# protractor.net
KiCad netlist of a schematic drawn in EAGLE
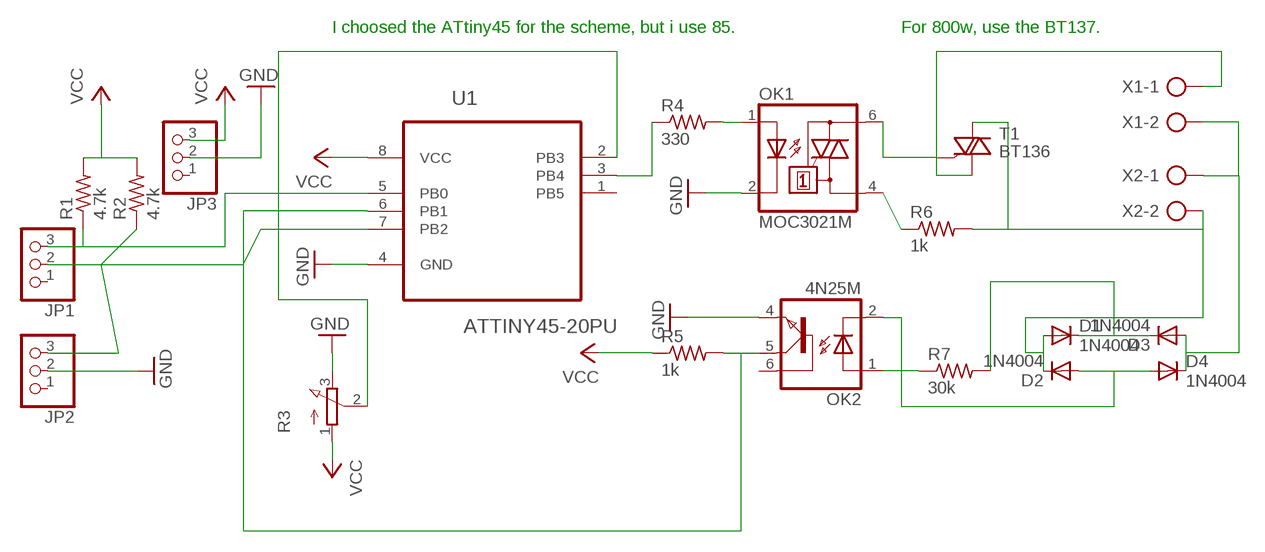
[diagram p0: schematic, sheet 1]

(export (version "E")
  (design (tool "Eeschema 10.0.6"))
  (components
    (comp (ref "D1")
      (value "1N4004")
      (footprint "eagle-import:DO41-10")
      (libsource (lib "eagle-import") (part "1N4004"))
    )
    (comp (ref "D2")
      (value "1N4004")
      (footprint "eagle-import:DO41-10")
      (libsource (lib "eagle-import") (part "1N4004"))
    )
    (comp (ref "D3")
      (value "1N4004")
      (footprint "eagle-import:DO41-10")
      (libsource (lib "eagle-import") (part "1N4004"))
    )
    (comp (ref "D4")
      (value "1N4004")
      (footprint "eagle-import:DO41-10")
      (libsource (lib "eagle-import") (part "1N4004"))
    )
    (comp (ref "JP1")
      (value "PINHD-1X3")
      (footprint "eagle-import:1X03")
      (libsource (lib "eagle-import") (part "PINHD-1X3"))
    )
    (comp (ref "JP2")
      (value "PINHD-1X3")
      (footprint "eagle-import:1X03")
      (libsource (lib "eagle-import") (part "PINHD-1X3"))
    )
    (comp (ref "JP3")
      (value "PINHD-1X3")
      (footprint "eagle-import:1X03")
      (libsource (lib "eagle-import") (part "PINHD-1X3"))
    )
    (comp (ref "OK1")
      (value "MOC3021M")
      (footprint "eagle-import:DIL06")
      (fields (field (name "MF") "FAIRCHILD SEMICONDUCTOR") (field (name "MPN") "MOC3021-M"))
      (libsource (lib "eagle-import") (part "MOC30M21"))
    )
    (comp (ref "OK2")
      (value "4N25M")
      (footprint "eagle-import:DIL06")
      (fields (field (name "MPN") "4N25-M"))
      (libsource (lib "eagle-import") (part "4N?M25"))
    )
    (comp (ref "R1")
      (value "4.7k")
      (footprint "eagle-import:0207_12")
      (libsource (lib "eagle-import") (part "R-US_0207/12"))
    )
    (comp (ref "R2")
      (value "4.7k")
      (footprint "eagle-import:0207_12")
      (libsource (lib "eagle-import") (part "R-US_0207/12"))
    )
    (comp (ref "R3")
      (value "3RP/1610N")
      (footprint "eagle-import:3RP_1610N")
      (libsource (lib "eagle-import") (part "3RP/1610N"))
    )
    (comp (ref "R4")
      (value "330")
      (footprint "eagle-import:0207_12")
      (libsource (lib "eagle-import") (part "R-US_0207/12"))
    )
    (comp (ref "R5")
      (value "1k")
      (footprint "eagle-import:0207_12")
      (libsource (lib "eagle-import") (part "R-US_0207/12"))
    )
    (comp (ref "R6")
      (value "1k")
      (footprint "eagle-import:0207_12")
      (libsource (lib "eagle-import") (part "R-US_0207/12"))
    )
    (comp (ref "R7")
      (value "30k")
      (footprint "eagle-import:0207_12")
      (libsource (lib "eagle-import") (part "R-US_0207/12"))
    )
    (comp (ref "T1")
      (value "BT136")
      (footprint "eagle-import:TO220AB")
      (libsource (lib "eagle-import") (part "BT136"))
    )
    (comp (ref "U1")
      (value "ATTINY45-20PU")
      (footprint "eagle-import:DIP254P762X533-8")
      (libsource (lib "eagle-import") (part "ATTINY45-20PU"))
    )
    (comp (ref "X1")
      (value "AK500/2-H")
      (footprint "eagle-import:AK500_2-H")
      (libsource (lib "eagle-import") (part "AK500/2-H"))
    )
    (comp (ref "X2")
      (value "AK500/2-H")
      (footprint "eagle-import:AK500_2-H")
      (libsource (lib "eagle-import") (part "AK500/2-H"))
    )
  )
  (nets
    (net (code "1") (name "GND") (class "Default")
      (node (ref "JP2") (pin "2") (pinfunction "2_2") (pintype "passive"))
      (node (ref "JP3") (pin "2") (pinfunction "2_2") (pintype "passive"))
      (node (ref "OK1") (pin "2") (pinfunction "C_2") (pintype "passive"))
      (node (ref "OK2") (pin "4") (pinfunction "EMI_4") (pintype "passive"))
      (node (ref "R3") (pin "3") (pinfunction "E_3") (pintype "passive"))
      (node (ref "U1") (pin "4") (pinfunction "GND_4") (pintype "passive"))
    )
    (net (code "2") (name "Net-(D1-PadC)") (class "Default")
      (node (ref "D1") (pin "C") (pinfunction "C_C") (pintype "passive"))
      (node (ref "D3") (pin "C") (pinfunction "C_C") (pintype "passive"))
      (node (ref "R7") (pin "2") (pinfunction "2_2") (pintype "passive"))
    )
    (net (code "3") (name "Net-(OK1-A)") (class "Default")
      (node (ref "OK1") (pin "1") (pinfunction "A_1") (pintype "passive"))
      (node (ref "R4") (pin "2") (pinfunction "2_2") (pintype "passive"))
    )
    (net (code "4") (name "Net-(OK1-A1)") (class "Default")
      (node (ref "OK1") (pin "4") (pinfunction "A1_4") (pintype "passive"))
      (node (ref "R6") (pin "1") (pinfunction "1_1") (pintype "passive"))
    )
    (net (code "5") (name "Net-(OK1-A2)") (class "Default")
      (node (ref "OK1") (pin "6") (pinfunction "A2_6") (pintype "passive"))
      (node (ref "T1") (pin "3") (pinfunction "G_3") (pintype "passive"))
    )
    (net (code "6") (name "Net-(OK2-A)") (class "Default")
      (node (ref "OK2") (pin "1") (pinfunction "A_1") (pintype "passive"))
      (node (ref "R7") (pin "1") (pinfunction "1_1") (pintype "passive"))
    )
    (net (code "7") (name "Net-(OK2-C)") (class "Default")
      (node (ref "D2") (pin "A") (pinfunction "A_A") (pintype "passive"))
      (node (ref "D4") (pin "A") (pinfunction "A_A") (pintype "passive"))
      (node (ref "OK2") (pin "2") (pinfunction "C_2") (pintype "passive"))
    )
    (net (code "8") (name "Net-(OK2-COL)") (class "Default")
      (node (ref "OK2") (pin "5") (pinfunction "COL_5") (pintype "passive"))
      (node (ref "R5") (pin "2") (pinfunction "2_2") (pintype "passive"))
      (node (ref "U1") (pin "6") (pinfunction "PB1_6") (pintype "bidirectional"))
    )
    (net (code "9") (name "Net-(R3-S)") (class "Default")
      (node (ref "R3") (pin "2") (pinfunction "S_2") (pintype "passive"))
      (node (ref "U1") (pin "2") (pinfunction "PB3_2") (pintype "bidirectional"))
    )
    (net (code "10") (name "Net-(T1-A1)") (class "Default")
      (node (ref "T1") (pin "1") (pinfunction "A1_1") (pintype "passive"))
      (node (ref "X1") (pin "1") (pinfunction "KL_1") (pintype "passive"))
    )
    (net (code "11") (name "Net-(T1-A2)") (class "Default")
      (node (ref "D1") (pin "A") (pinfunction "A_A") (pintype "passive"))
      (node (ref "D2") (pin "C") (pinfunction "C_C") (pintype "passive"))
      (node (ref "R6") (pin "2") (pinfunction "2_2") (pintype "passive"))
      (node (ref "T1") (pin "2") (pinfunction "A2_2") (pintype "passive"))
      (node (ref "X2") (pin "2") (pinfunction "KL_2") (pintype "passive"))
    )
    (net (code "12") (name "Net-(U1-PB0)") (class "Default")
      (node (ref "JP1") (pin "3") (pinfunction "3_3") (pintype "passive"))
      (node (ref "R1") (pin "1") (pinfunction "1_1") (pintype "passive"))
      (node (ref "U1") (pin "5") (pinfunction "PB0_5") (pintype "bidirectional"))
    )
    (net (code "13") (name "Net-(U1-PB2)") (class "Default")
      (node (ref "JP1") (pin "2") (pinfunction "2_2") (pintype "passive"))
      (node (ref "JP2") (pin "3") (pinfunction "3_3") (pintype "passive"))
      (node (ref "R2") (pin "1") (pinfunction "1_1") (pintype "passive"))
      (node (ref "U1") (pin "7") (pinfunction "PB2_7") (pintype "bidirectional"))
    )
    (net (code "14") (name "Net-(U1-PB4)") (class "Default")
      (node (ref "R4") (pin "1") (pinfunction "1_1") (pintype "passive"))
      (node (ref "U1") (pin "3") (pinfunction "PB4_3") (pintype "bidirectional"))
    )
    (net (code "15") (name "Net-(X1B-KL)") (class "Default")
      (node (ref "D3") (pin "A") (pinfunction "A_A") (pintype "passive"))
      (node (ref "D4") (pin "C") (pinfunction "C_C") (pintype "passive"))
      (node (ref "X1") (pin "2") (pinfunction "KL_2") (pintype "passive"))
      (node (ref "X2") (pin "1") (pinfunction "KL_1") (pintype "passive"))
    )
    (net (code "16") (name "VCC") (class "Default")
      (node (ref "JP3") (pin "3") (pinfunction "3_3") (pintype "passive"))
      (node (ref "R1") (pin "2") (pinfunction "2_2") (pintype "passive"))
      (node (ref "R2") (pin "2") (pinfunction "2_2") (pintype "passive"))
      (node (ref "R3") (pin "1") (pinfunction "A_1") (pintype "passive"))
      (node (ref "R5") (pin "1") (pinfunction "1_1") (pintype "passive"))
      (node (ref "U1") (pin "8") (pinfunction "VCC_8") (pintype "power_in"))
    )
    (net (code "17") (name "unconnected-(JP1-Pad1)") (class "Default")
      (node (ref "JP1") (pin "1") (pinfunction "1_1") (pintype "passive"))
    )
    (net (code "18") (name "unconnected-(JP2-Pad1)") (class "Default")
      (node (ref "JP2") (pin "1") (pinfunction "1_1") (pintype "passive"))
    )
    (net (code "19") (name "unconnected-(JP3-Pad1)") (class "Default")
      (node (ref "JP3") (pin "1") (pinfunction "1_1") (pintype "passive"))
    )
    (net (code "20") (name "unconnected-(OK2-BAS-Pad6)") (class "Default")
      (node (ref "OK2") (pin "6") (pinfunction "BAS_6") (pintype "passive"))
    )
    (net (code "21") (name "unconnected-(U1-PB5-Pad1)") (class "Default")
      (node (ref "U1") (pin "1") (pinfunction "PB5_1") (pintype "bidirectional"))
    )
  )
)
